# -_4-11.net
KiCad netlist of a schematic drawn in EasyEDA Pro
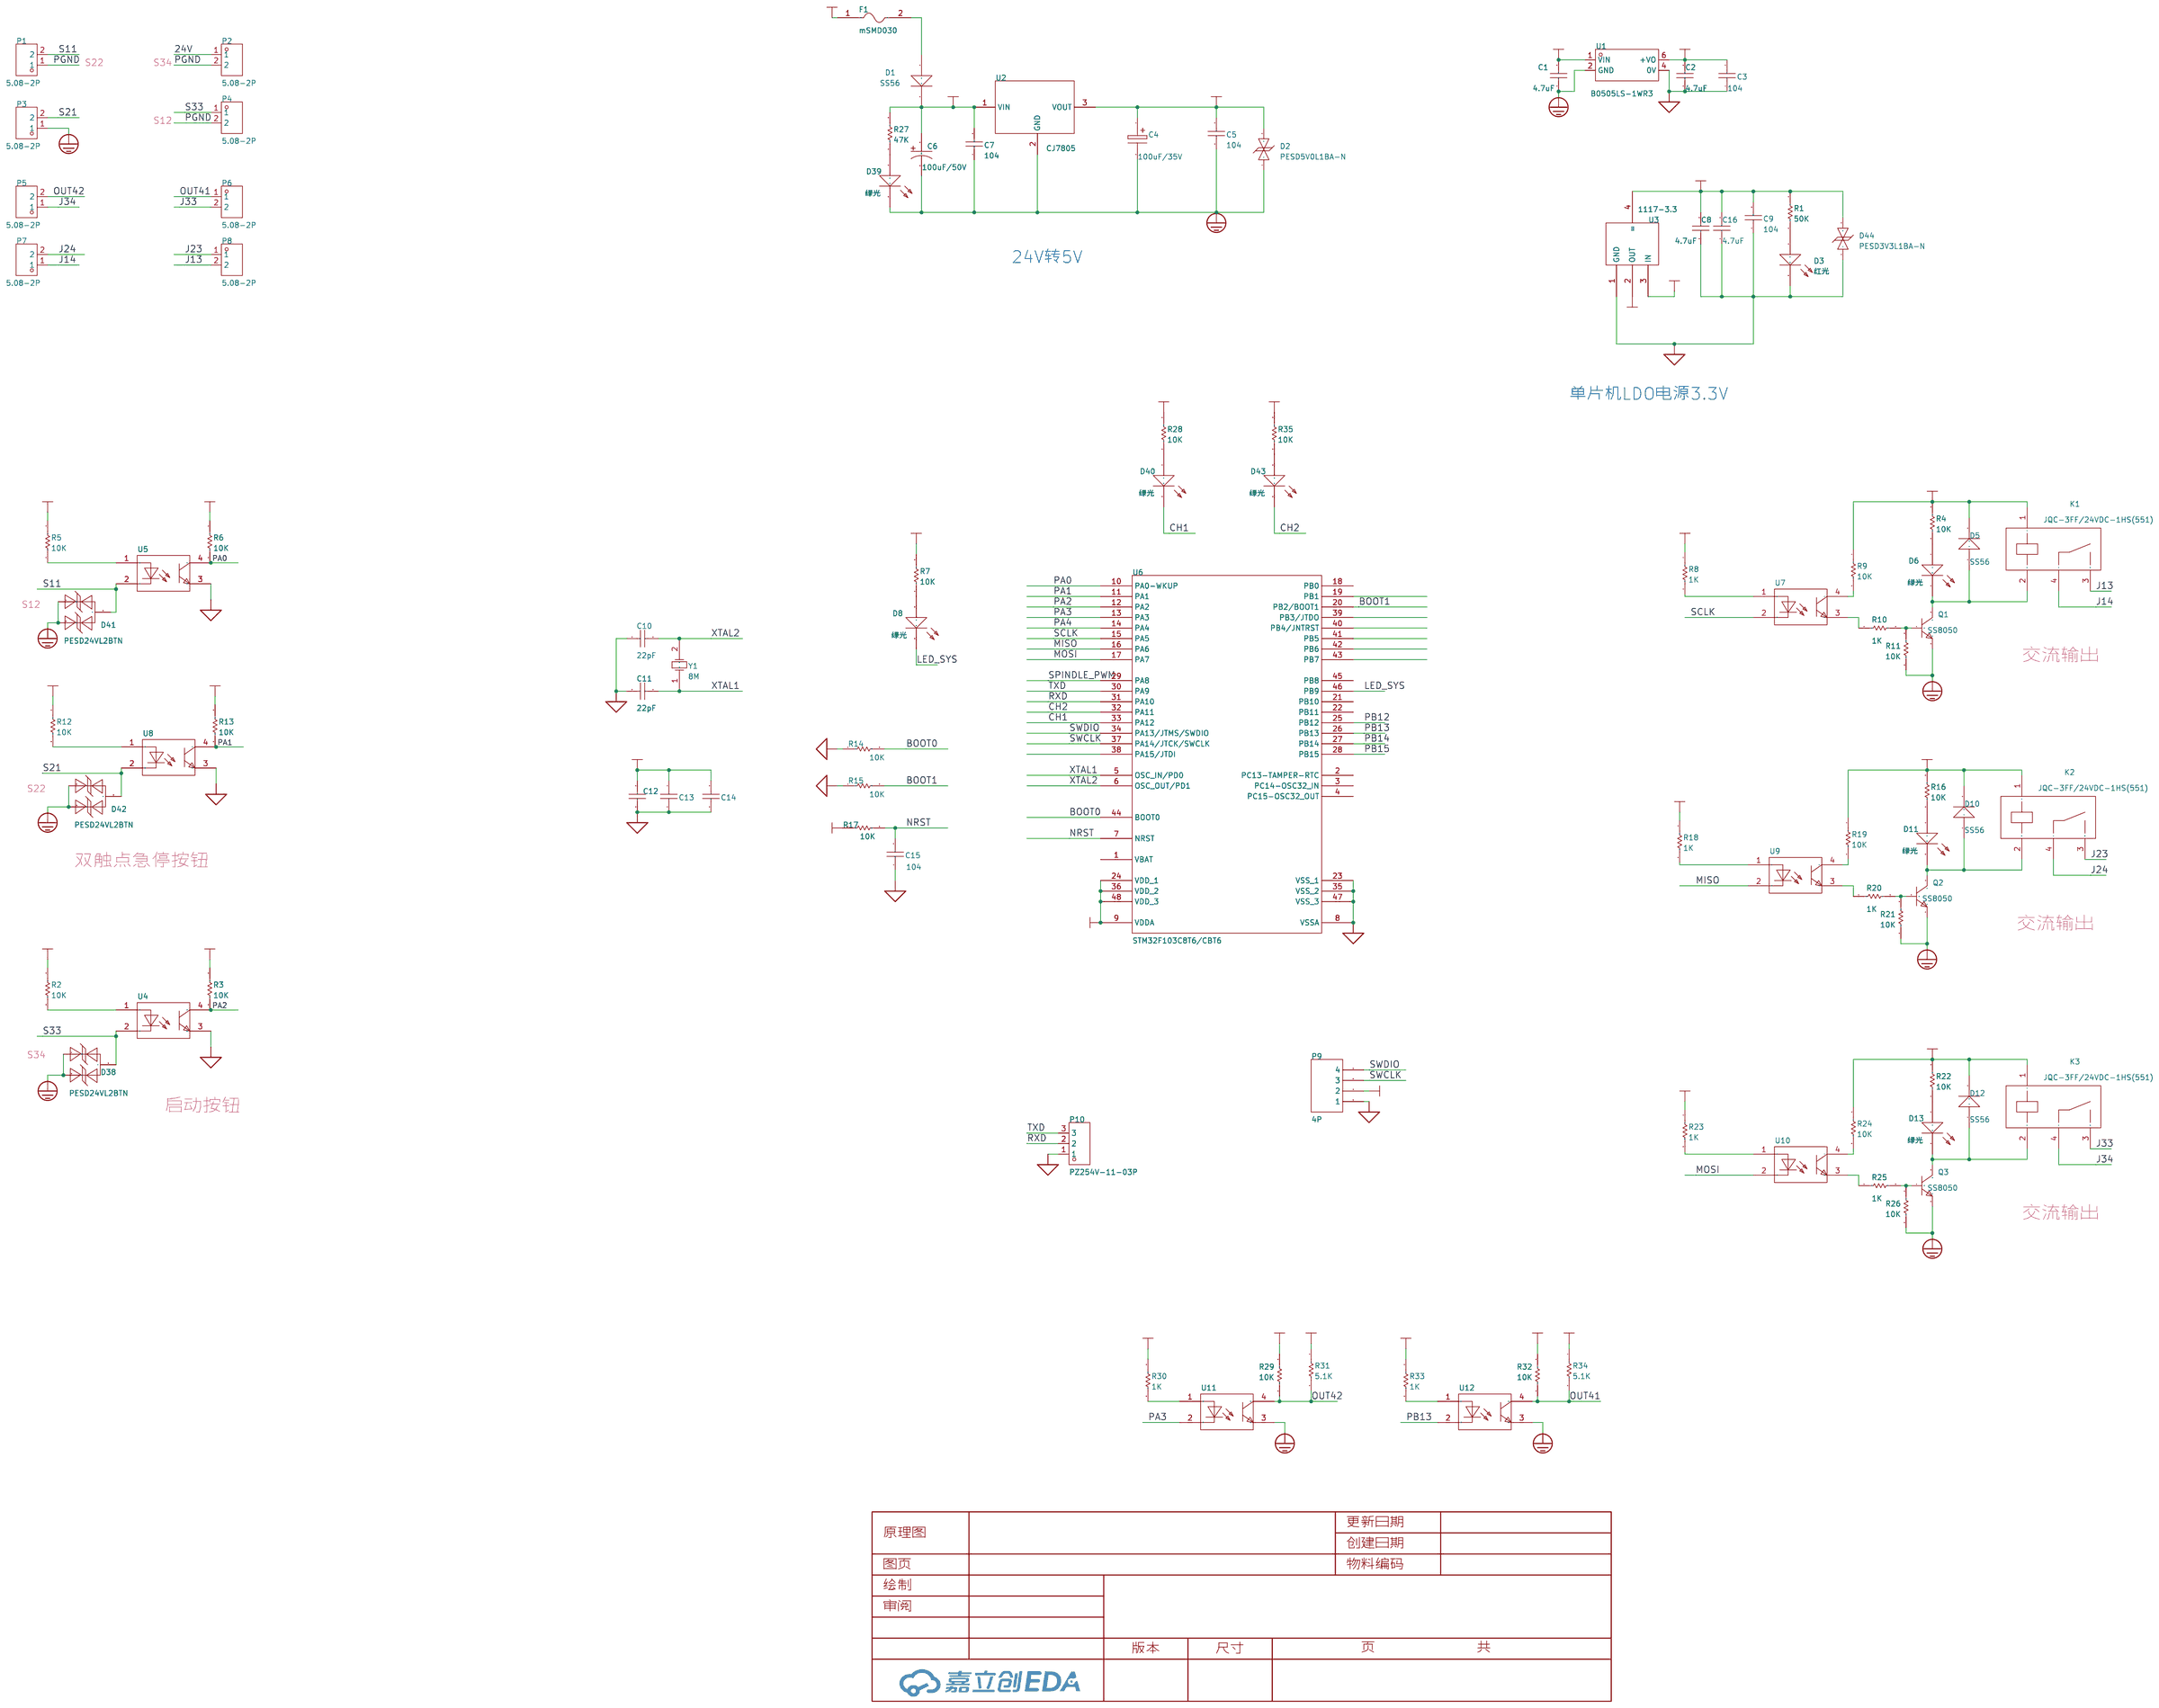
[diagram p0: 主控MCU]
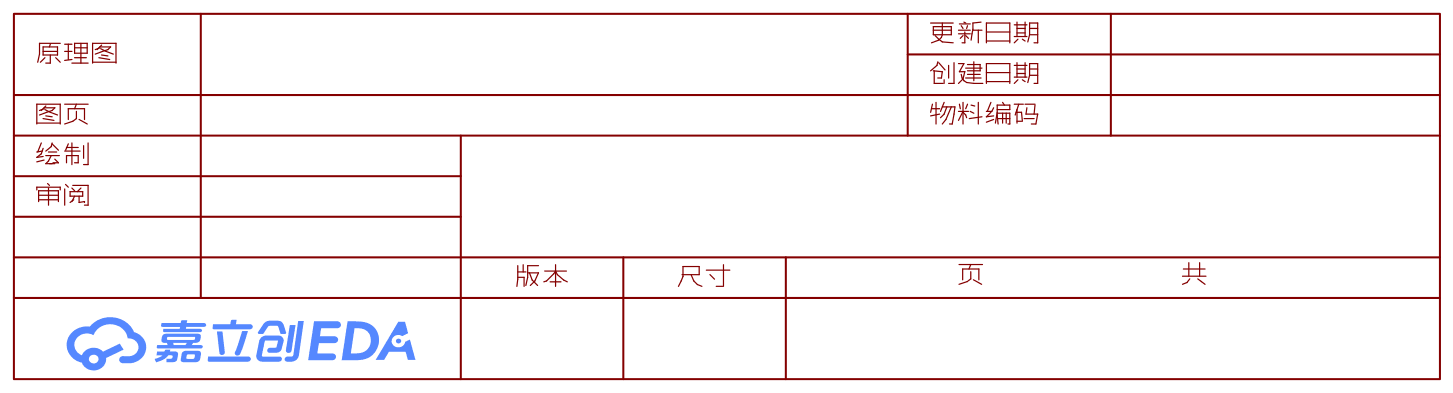
[diagram p1: 电源及控制]

(export (version "E")
  (design (tool "Eeschema 10.0.6"))
  (components
    (comp (ref "C1") (value "4.7uF") (libsource (lib "") (part "CAP_1")))
    (comp (ref "C2") (value "4.7uF") (libsource (lib "") (part "CAP_1")))
    (comp (ref "C3") (value "104") (libsource (lib "") (part "CAP_1")))
    (comp (ref "C4")
      (value "100uF/35V")
      (footprint "easyedapro:0603C")
      (libsource (lib "easyedapro") (part "ELECTRO1"))
    )
    (comp (ref "C5")
      (value "104")
      (footprint "easyedapro:0603C")
      (description "Capacitor (Semiconductor SIM Model)")
      (libsource (lib "easyedapro") (part "Cap Semi"))
    )
    (comp (ref "C6")
      (value "100uF/50V")
      (footprint "easyedapro:CAP-SMD_BD10.0-L10.3-W10.3-LS11.0-R-RD")
      (fields (field (name "Manufacturer Part") "VZH101M1HTR-1008") (field (name "Manufacturer") "lelon(立隆)"))
      (libsource (lib "easyedapro") (part "VZH101M1HTR-1008"))
    )
    (comp (ref "C7")
      (value "104")
      (footprint "easyedapro:0603C")
      (description "Capacitor (Semiconductor SIM Model)")
      (libsource (lib "easyedapro") (part "Cap Semi"))
    )
    (comp (ref "C8") (value "4.7uF") (libsource (lib "") (part "CAP_1")))
    (comp (ref "C9")
      (value "104")
      (footprint "easyedapro:0603C")
      (description "Capacitor (Semiconductor SIM Model)")
      (libsource (lib "easyedapro") (part "Cap Semi"))
    )
    (comp (ref "C10")
      (value "100pF")
      (footprint "easyedapro:0603C")
      (description "Capacitor (Semiconductor SIM Model)")
      (libsource (lib "easyedapro") (part "Cap Semi"))
    )
    (comp (ref "C11")
      (value "100pF")
      (footprint "easyedapro:0603C")
      (description "Capacitor (Semiconductor SIM Model)")
      (libsource (lib "easyedapro") (part "Cap Semi"))
    )
    (comp (ref "C12")
      (value "104")
      (footprint "easyedapro:电解电容贴片6X6")
      (libsource (lib "easyedapro") (part "CAP"))
    )
    (comp (ref "C13")
      (value "104")
      (footprint "easyedapro:电解电容贴片6X6")
      (libsource (lib "easyedapro") (part "CAP"))
    )
    (comp (ref "C14")
      (value "104")
      (footprint "easyedapro:电解电容贴片6X6")
      (libsource (lib "easyedapro") (part "CAP"))
    )
    (comp (ref "C15")
      (value "104")
      (footprint "easyedapro:0603C")
      (description "Capacitor (Semiconductor SIM Model)")
      (libsource (lib "easyedapro") (part "Cap Semi"))
    )
    (comp (ref "C16") (value "4.7uF") (libsource (lib "") (part "CAP_1")))
    (comp (ref "D1")
      (value "SS56")
      (footprint "easyedapro:SMA")
      (libsource (lib "easyedapro") (part "1N4148"))
    )
    (comp (ref "D2")
      (value "PESD5V0L1BA-N")
      (footprint "easyedapro:SOD-523_L1.2-W0.8-LS1.6-BI")
      (description "极性:Bidirectional;反向关断电压（典型值）:5V (Max);击穿电压（最小值）:6V;箝位电压:15V;峰值脉冲电流（10/1000us）:5A (8/20us);")
      (fields (field (name "Manufacturer") "BORN伯恩半导体"))
      (libsource (lib "easyedapro") (part "PESD5V0S1BBN"))
    )
    (comp (ref "D3")
      (value "红光")
      (footprint "easyedapro:0603LED")
      (libsource (lib "easyedapro") (part "LED"))
    )
    (comp (ref "D5")
      (value "SS56")
      (footprint "easyedapro:SMA")
      (libsource (lib "easyedapro") (part "1N4148"))
    )
    (comp (ref "D6")
      (value "绿光")
      (footprint "easyedapro:0603LED")
      (libsource (lib "easyedapro") (part "LED"))
    )
    (comp (ref "D8")
      (value "绿光")
      (footprint "easyedapro:0603LED")
      (libsource (lib "easyedapro") (part "LED"))
    )
    (comp (ref "D10")
      (value "SS56")
      (footprint "easyedapro:SMA")
      (libsource (lib "easyedapro") (part "1N4148"))
    )
    (comp (ref "D11")
      (value "绿光")
      (footprint "easyedapro:0603LED")
      (libsource (lib "easyedapro") (part "LED"))
    )
    (comp (ref "D12")
      (value "SS56")
      (footprint "easyedapro:SMA")
      (libsource (lib "easyedapro") (part "1N4148"))
    )
    (comp (ref "D13")
      (value "绿光")
      (footprint "easyedapro:0603LED")
      (libsource (lib "easyedapro") (part "LED"))
    )
    (comp (ref "D38")
      (value "PESD24VL2BTN")
      (footprint "easyedapro:SOT-23-3_L2.9-W1.6-P1.90-LS2.8-BR")
      (description "极性:Bidirectional;反向关断电压（典型值）:24V (Max);击穿电压（最小值）:26.7V;箝位电压:48V;峰值脉冲电流（10/1000us）:6A (8/20us);")
      (fields (field (name "Manufacturer") "BORN伯恩半导体"))
      (libsource (lib "easyedapro") (part "PESD24VL2BTN"))
    )
    (comp (ref "D39")
      (value "绿光")
      (footprint "easyedapro:0603LED")
      (libsource (lib "easyedapro") (part "LED"))
    )
    (comp (ref "D40")
      (value "绿光")
      (footprint "easyedapro:0603LED")
      (libsource (lib "easyedapro") (part "LED"))
    )
    (comp (ref "D41")
      (value "PESD24VL2BTN")
      (footprint "easyedapro:SOT-23-3_L2.9-W1.6-P1.90-LS2.8-BR")
      (description "极性:Bidirectional;反向关断电压（典型值）:24V (Max);击穿电压（最小值）:26.7V;箝位电压:48V;峰值脉冲电流（10/1000us）:6A (8/20us);")
      (fields (field (name "Manufacturer") "BORN伯恩半导体"))
      (libsource (lib "easyedapro") (part "PESD24VL2BTN"))
    )
    (comp (ref "D42")
      (value "PESD24VL2BTN")
      (footprint "easyedapro:SOT-23-3_L2.9-W1.6-P1.90-LS2.8-BR")
      (description "极性:Bidirectional;反向关断电压（典型值）:24V (Max);击穿电压（最小值）:26.7V;箝位电压:48V;峰值脉冲电流（10/1000us）:6A (8/20us);")
      (fields (field (name "Manufacturer") "BORN伯恩半导体"))
      (libsource (lib "easyedapro") (part "PESD24VL2BTN"))
    )
    (comp (ref "D43")
      (value "绿光")
      (footprint "easyedapro:0603LED")
      (libsource (lib "easyedapro") (part "LED"))
    )
    (comp (ref "D44")
      (value "PESD3V3L1BA-N")
      (footprint "easyedapro:SOD-523_L1.2-W0.8-LS1.6-BI")
      (description "极性:Bidirectional;反向关断电压（典型值）:5V (Max);击穿电压（最小值）:6V;箝位电压:15V;峰值脉冲电流（10/1000us）:5A (8/20us);")
      (fields (field (name "Manufacturer") "BORN伯恩半导体"))
      (libsource (lib "easyedapro") (part "PESD5V0S1BBN"))
    )
    (comp (ref "F1")
      (value "mSMD030")
      (footprint "easyedapro:F1812")
      (description "最大电压:30V;最大电流:100A;保持电流:300mA;跳闸电流:600mA;")
      (fields (field (name "Manufacturer") "台湾陆海"))
      (libsource (lib "easyedapro") (part "mSMD030"))
    )
    (comp (ref "K1")
      (value "JQC-3FF/24VDC-1HS(551)")
      (footprint "easyedapro:RELAY-TH_JQC-3FF-1HXX")
      (description "继电器类型:General Purpose;线圈类型:Non Latching;线圈电压:24VDC;触点形式:SPST-NO;触点的额定电流:15A;")
      (fields (field (name "Manufacturer") "HF(宏发)"))
      (libsource (lib "easyedapro") (part "JQC-3FF/024-1HS"))
    )
    (comp (ref "K2")
      (value "JQC-3FF/24VDC-1HS(551)")
      (footprint "easyedapro:RELAY-TH_JQC-3FF-1HXX")
      (description "继电器类型:General Purpose;线圈类型:Non Latching;线圈电压:24VDC;触点形式:SPST-NO;触点的额定电流:15A;")
      (fields (field (name "Manufacturer") "HF(宏发)"))
      (libsource (lib "easyedapro") (part "JQC-3FF/024-1HS"))
    )
    (comp (ref "K3")
      (value "JQC-3FF/24VDC-1HS(551)")
      (footprint "easyedapro:RELAY-TH_JQC-3FF-1HXX")
      (description "继电器类型:General Purpose;线圈类型:Non Latching;线圈电压:24VDC;触点形式:SPST-NO;触点的额定电流:15A;")
      (fields (field (name "Manufacturer") "HF(宏发)"))
      (libsource (lib "easyedapro") (part "JQC-3FF/024-1HS"))
    )
    (comp (ref "P1")
      (value "5.08-2P")
      (footprint "easyedapro:CONN-TH_2P-P5.08_DB128L-5.08-2P")
      (fields (field (name "Manufacturer") "DIBO(地博电气)"))
      (libsource (lib "easyedapro") (part "DB128L-5.08-2P"))
    )
    (comp (ref "P2")
      (value "5.08-2P")
      (footprint "easyedapro:CONN-TH_2P-P5.08_DB128L-5.08-2P")
      (fields (field (name "Manufacturer") "DIBO(地博电气)"))
      (libsource (lib "easyedapro") (part "DB128L-5.08-2P"))
    )
    (comp (ref "P3")
      (value "5.08-2P")
      (footprint "easyedapro:CONN-TH_2P-P5.08_DB128L-5.08-2P")
      (fields (field (name "Manufacturer") "DIBO(地博电气)"))
      (libsource (lib "easyedapro") (part "DB128L-5.08-2P"))
    )
    (comp (ref "P4")
      (value "5.08-2P")
      (footprint "easyedapro:CONN-TH_2P-P5.08_DB128L-5.08-2P")
      (fields (field (name "Manufacturer") "DIBO(地博电气)"))
      (libsource (lib "easyedapro") (part "DB128L-5.08-2P"))
    )
    (comp (ref "P5")
      (value "5.08-2P")
      (footprint "easyedapro:CONN-TH_2P-P5.08_DB128L-5.08-2P")
      (fields (field (name "Manufacturer") "DIBO(地博电气)"))
      (libsource (lib "easyedapro") (part "DB128L-5.08-2P"))
    )
    (comp (ref "P6")
      (value "5.08-2P")
      (footprint "easyedapro:CONN-TH_2P-P5.08_DB128L-5.08-2P")
      (fields (field (name "Manufacturer") "DIBO(地博电气)"))
      (libsource (lib "easyedapro") (part "DB128L-5.08-2P"))
    )
    (comp (ref "P7")
      (value "5.08-2P")
      (footprint "easyedapro:CONN-TH_2P-P5.08_DB128L-5.08-2P")
      (fields (field (name "Manufacturer") "DIBO(地博电气)"))
      (libsource (lib "easyedapro") (part "DB128L-5.08-2P"))
    )
    (comp (ref "P8")
      (value "5.08-2P")
      (footprint "easyedapro:CONN-TH_2P-P5.08_DB128L-5.08-2P")
      (fields (field (name "Manufacturer") "DIBO(地博电气)"))
      (libsource (lib "easyedapro") (part "DB128L-5.08-2P"))
    )
    (comp (ref "P9") (value "4P") (libsource (lib "easyedapro") (part "4P")))
    (comp (ref "P10")
      (value "PZ254V-11-03P")
      (footprint "easyedapro:HDR-TH_3P-P2.54-V-M")
      (fields (field (name "Manufacturer") "XFCN(兴飞)"))
      (libsource (lib "easyedapro") (part "PZ254V-11-03P_C2937625"))
    )
    (comp (ref "Q1")
      (value "SS8050")
      (footprint "easyedapro:SOT-23-3_L2.9-W1.3-P1.90-LS2.4-BR")
      (fields (field (name "Manufacturer") "CJ（江苏长电/长晶）"))
      (libsource (lib "easyedapro") (part "SS8050_C2150"))
    )
    (comp (ref "Q2")
      (value "SS8050")
      (footprint "easyedapro:SOT-23-3_L2.9-W1.3-P1.90-LS2.4-BR")
      (fields (field (name "Manufacturer") "CJ（江苏长电/长晶）"))
      (libsource (lib "easyedapro") (part "SS8050_C2150"))
    )
    (comp (ref "Q3")
      (value "SS8050")
      (footprint "easyedapro:SOT-23-3_L2.9-W1.3-P1.90-LS2.4-BR")
      (fields (field (name "Manufacturer") "CJ（江苏长电/长晶）"))
      (libsource (lib "easyedapro") (part "SS8050_C2150"))
    )
    (comp (ref "R1")
      (value "50K")
      (footprint "easyedapro:0603R")
      (description "Resistor")
      (libsource (lib "easyedapro") (part "RES"))
    )
    (comp (ref "R2")
      (value "10K")
      (footprint "easyedapro:0603R")
      (description "Resistor")
      (libsource (lib "easyedapro") (part "RES"))
    )
    (comp (ref "R3")
      (value "10K")
      (footprint "easyedapro:0603R")
      (description "Resistor")
      (libsource (lib "easyedapro") (part "RES"))
    )
    (comp (ref "R4")
      (value "10K")
      (footprint "easyedapro:0603R")
      (description "Resistor")
      (libsource (lib "easyedapro") (part "RES"))
    )
    (comp (ref "R5")
      (value "10K")
      (footprint "easyedapro:0603R")
      (description "Resistor")
      (libsource (lib "easyedapro") (part "RES"))
    )
    (comp (ref "R6")
      (value "10K")
      (footprint "easyedapro:0603R")
      (description "Resistor")
      (libsource (lib "easyedapro") (part "RES"))
    )
    (comp (ref "R7")
      (value "10K")
      (footprint "easyedapro:0603R")
      (description "Resistor")
      (libsource (lib "easyedapro") (part "RES"))
    )
    (comp (ref "R8")
      (value "1K")
      (footprint "easyedapro:0603R")
      (description "Resistor")
      (libsource (lib "easyedapro") (part "RES"))
    )
    (comp (ref "R9")
      (value "10K")
      (footprint "easyedapro:0603R")
      (description "Resistor")
      (libsource (lib "easyedapro") (part "RES"))
    )
    (comp (ref "R10")
      (value "1K")
      (footprint "easyedapro:0603R")
      (description "Resistor")
      (libsource (lib "easyedapro") (part "RES"))
    )
    (comp (ref "R11")
      (value "10K")
      (footprint "easyedapro:0603R")
      (description "Resistor")
      (libsource (lib "easyedapro") (part "RES"))
    )
    (comp (ref "R12")
      (value "10K")
      (footprint "easyedapro:0603R")
      (description "Resistor")
      (libsource (lib "easyedapro") (part "RES"))
    )
    (comp (ref "R13")
      (value "10K")
      (footprint "easyedapro:0603R")
      (description "Resistor")
      (libsource (lib "easyedapro") (part "RES"))
    )
    (comp (ref "R14")
      (value "10K")
      (footprint "easyedapro:0603R")
      (description "Resistor")
      (libsource (lib "easyedapro") (part "RES"))
    )
    (comp (ref "R15")
      (value "10K")
      (footprint "easyedapro:0603R")
      (description "Resistor")
      (libsource (lib "easyedapro") (part "RES"))
    )
    (comp (ref "R16")
      (value "10K")
      (footprint "easyedapro:0603R")
      (description "Resistor")
      (libsource (lib "easyedapro") (part "RES"))
    )
    (comp (ref "R17")
      (value "10K")
      (footprint "easyedapro:0603R")
      (description "Resistor")
      (libsource (lib "easyedapro") (part "RES"))
    )
    (comp (ref "R18")
      (value "1K")
      (footprint "easyedapro:0603R")
      (description "Resistor")
      (libsource (lib "easyedapro") (part "RES"))
    )
    (comp (ref "R19")
      (value "10K")
      (footprint "easyedapro:0603R")
      (description "Resistor")
      (libsource (lib "easyedapro") (part "RES"))
    )
    (comp (ref "R20")
      (value "1K")
      (footprint "easyedapro:0603R")
      (description "Resistor")
      (libsource (lib "easyedapro") (part "RES"))
    )
    (comp (ref "R21")
      (value "10K")
      (footprint "easyedapro:0603R")
      (description "Resistor")
      (libsource (lib "easyedapro") (part "RES"))
    )
    (comp (ref "R22")
      (value "10K")
      (footprint "easyedapro:0603R")
      (description "Resistor")
      (libsource (lib "easyedapro") (part "RES"))
    )
    (comp (ref "R23")
      (value "1K")
      (footprint "easyedapro:0603R")
      (description "Resistor")
      (libsource (lib "easyedapro") (part "RES"))
    )
    (comp (ref "R24")
      (value "10K")
      (footprint "easyedapro:0603R")
      (description "Resistor")
      (libsource (lib "easyedapro") (part "RES"))
    )
    (comp (ref "R25")
      (value "1K")
      (footprint "easyedapro:0603R")
      (description "Resistor")
      (libsource (lib "easyedapro") (part "RES"))
    )
    (comp (ref "R26")
      (value "10K")
      (footprint "easyedapro:0603R")
      (description "Resistor")
      (libsource (lib "easyedapro") (part "RES"))
    )
    (comp (ref "R27")
      (value "47K")
      (footprint "easyedapro:0603R")
      (description "Resistor")
      (libsource (lib "easyedapro") (part "RES"))
    )
    (comp (ref "R28")
      (value "10K")
      (footprint "easyedapro:0603R")
      (description "Resistor")
      (libsource (lib "easyedapro") (part "RES"))
    )
    (comp (ref "R29")
      (value "10K")
      (footprint "easyedapro:0603R")
      (description "Resistor")
      (libsource (lib "easyedapro") (part "RES"))
    )
    (comp (ref "R30")
      (value "1K")
      (footprint "easyedapro:0603R")
      (description "Resistor")
      (libsource (lib "easyedapro") (part "RES"))
    )
    (comp (ref "R31")
      (value "10K")
      (footprint "easyedapro:0603R")
      (description "Resistor")
      (libsource (lib "easyedapro") (part "RES"))
    )
    (comp (ref "R32")
      (value "10K")
      (footprint "easyedapro:0603R")
      (description "Resistor")
      (libsource (lib "easyedapro") (part "RES"))
    )
    (comp (ref "R33")
      (value "1K")
      (footprint "easyedapro:0603R")
      (description "Resistor")
      (libsource (lib "easyedapro") (part "RES"))
    )
    (comp (ref "R34")
      (value "10K")
      (footprint "easyedapro:0603R")
      (description "Resistor")
      (libsource (lib "easyedapro") (part "RES"))
    )
    (comp (ref "R35")
      (value "10K")
      (footprint "easyedapro:0603R")
      (description "Resistor")
      (libsource (lib "easyedapro") (part "RES"))
    )
    (comp (ref "U1")
      (value "B0505LS-1WR3")
      (footprint "easyedapro:PWRM-TH_BXXXXLS-1WR3")
      (description "100%国产化器件，高可靠性，具备ROHS、REACH、CE认证产品")
      (fields (field (name "Manufacturer") "DEXU(德旭电子)"))
      (libsource (lib "easyedapro") (part "B0505LS-1WR3_C909800"))
    )
    (comp (ref "U2")
      (value "CJ7805")
      (footprint "easyedapro:TO-263-2")
      (libsource (lib "easyedapro") (part "7805"))
    )
    (comp (ref "U3")
      (value "1117-3.3")
      (footprint "easyedapro:SOT-223")
      (libsource (lib "easyedapro") (part "LM1117"))
    )
    (comp (ref "U4")
      (value "LTV-357T-C")
      (footprint "easyedapro:SOP-4_L4.4-W3.9-P2.54-LS7.0-TL")
      (fields (field (name "Manufacturer") "LITEON(光宝)"))
      (libsource (lib "easyedapro") (part "LTV-357T-C"))
    )
    (comp (ref "U5")
      (value "LTV-357T-C")
      (footprint "easyedapro:SOP-4_L4.4-W3.9-P2.54-LS7.0-TL")
      (fields (field (name "Manufacturer") "LITEON(光宝)"))
      (libsource (lib "easyedapro") (part "LTV-357T-C"))
    )
    (comp (ref "U6")
      (value "STM32F103C8T6/CBT6")
      (footprint "easyedapro:LQFP48")
      (description "STM32 ARM-based 32-bit MCU with 32 Kbytes Flash, 48-pin LQFP, Industrial Temperature")
      (libsource (lib "easyedapro") (part "STM32F103C6T6"))
    )
    (comp (ref "U7")
      (value "LTV-357T-C")
      (footprint "easyedapro:SOP-4_L4.4-W3.9-P2.54-LS7.0-TL")
      (fields (field (name "Manufacturer") "LITEON(光宝)"))
      (libsource (lib "easyedapro") (part "LTV-357T-C"))
    )
    (comp (ref "U8")
      (value "LTV-357T-C")
      (footprint "easyedapro:SOP-4_L4.4-W3.9-P2.54-LS7.0-TL")
      (fields (field (name "Manufacturer") "LITEON(光宝)"))
      (libsource (lib "easyedapro") (part "LTV-357T-C"))
    )
    (comp (ref "U9")
      (value "LTV-357T-C")
      (footprint "easyedapro:SOP-4_L4.4-W3.9-P2.54-LS7.0-TL")
      (fields (field (name "Manufacturer") "LITEON(光宝)"))
      (libsource (lib "easyedapro") (part "LTV-357T-C"))
    )
    (comp (ref "U10")
      (value "LTV-357T-C")
      (footprint "easyedapro:SOP-4_L4.4-W3.9-P2.54-LS7.0-TL")
      (fields (field (name "Manufacturer") "LITEON(光宝)"))
      (libsource (lib "easyedapro") (part "LTV-357T-C"))
    )
    (comp (ref "U11")
      (value "LTV-357T-C")
      (footprint "easyedapro:SOP-4_L4.4-W3.9-P2.54-LS7.0-TL")
      (fields (field (name "Manufacturer") "LITEON(光宝)"))
      (libsource (lib "easyedapro") (part "LTV-357T-C"))
    )
    (comp (ref "U12")
      (value "LTV-357T-C")
      (footprint "easyedapro:SOP-4_L4.4-W3.9-P2.54-LS7.0-TL")
      (fields (field (name "Manufacturer") "LITEON(光宝)"))
      (libsource (lib "easyedapro") (part "LTV-357T-C"))
    )
    (comp (ref "Y1")
      (value "8M")
      (footprint "easyedapro:晶振贴片49SSMD")
      (description "Crystal Oscillator")
      (libsource (lib "easyedapro") (part "XTAL"))
    )
  )
  (nets
    (net (code "1") (name "3V3") (class "Default")
      (node (ref "C12") (pin "2") (pinfunction "2_2") (pintype "unspecified"))
      (node (ref "C13") (pin "2") (pinfunction "2_2") (pintype "unspecified"))
      (node (ref "C14") (pin "2") (pinfunction "2_2") (pintype "unspecified"))
      (node (ref "C16") (pin "2") (pinfunction "2_2") (pintype "input"))
      (node (ref "C8") (pin "2") (pinfunction "2_2") (pintype "input"))
      (node (ref "C9") (pin "2") (pinfunction "2_2") (pintype "unspecified"))
      (node (ref "D44") (pin "2") (pinfunction "2_2") (pintype "input"))
      (node (ref "P9") (pin "2") (pinfunction "2_2") (pintype "input"))
      (node (ref "R1") (pin "1") (pinfunction "1_1") (pintype "unspecified"))
      (node (ref "R13") (pin "1") (pinfunction "1_1") (pintype "unspecified"))
      (node (ref "R17") (pin "1") (pinfunction "1_1") (pintype "unspecified"))
      (node (ref "R18") (pin "1") (pinfunction "1_1") (pintype "unspecified"))
      (node (ref "R23") (pin "1") (pinfunction "1_1") (pintype "unspecified"))
      (node (ref "R28") (pin "2") (pinfunction "2_2") (pintype "unspecified"))
      (node (ref "R3") (pin "1") (pinfunction "1_1") (pintype "unspecified"))
      (node (ref "R30") (pin "1") (pinfunction "1_1") (pintype "unspecified"))
      (node (ref "R33") (pin "1") (pinfunction "1_1") (pintype "unspecified"))
      (node (ref "R35") (pin "2") (pinfunction "2_2") (pintype "unspecified"))
      (node (ref "R6") (pin "1") (pinfunction "1_1") (pintype "unspecified"))
      (node (ref "R7") (pin "2") (pinfunction "2_2") (pintype "unspecified"))
      (node (ref "R8") (pin "1") (pinfunction "1_1") (pintype "unspecified"))
      (node (ref "U3") (pin "2") (pinfunction "OUT_2") (pintype "unspecified"))
      (node (ref "U3") (pin "4") (pinfunction "=_4") (pintype "unspecified"))
      (node (ref "U6") (pin "24") (pinfunction "VDD_1_24") (pintype "unspecified"))
      (node (ref "U6") (pin "36") (pinfunction "VDD_2_36") (pintype "unspecified"))
      (node (ref "U6") (pin "48") (pinfunction "VDD_3_48") (pintype "unspecified"))
      (node (ref "U6") (pin "9") (pinfunction "VDDA_9") (pintype "unspecified"))
    )
    (net (code "2") (name "5V_MCU") (class "Default")
      (node (ref "C2") (pin "2") (pinfunction "2_2") (pintype "input"))
      (node (ref "C3") (pin "2") (pinfunction "2_2") (pintype "input"))
      (node (ref "U1") (pin "6") (pinfunction "+VO_6") (pintype "unspecified"))
      (node (ref "U3") (pin "3") (pinfunction "IN_3") (pintype "unspecified"))
    )
    (net (code "3") (name "5V_VCC") (class "Default")
      (node (ref "C1") (pin "2") (pinfunction "2_2") (pintype "input"))
      (node (ref "C4") (pin "1") (pintype "unspecified"))
      (node (ref "C5") (pin "2") (pinfunction "2_2") (pintype "unspecified"))
      (node (ref "D2") (pin "2") (pinfunction "2_2") (pintype "input"))
      (node (ref "R31") (pin "1") (pinfunction "1_1") (pintype "unspecified"))
      (node (ref "R34") (pin "1") (pinfunction "1_1") (pintype "unspecified"))
      (node (ref "U1") (pin "1") (pinfunction "VIN_1") (pintype "unspecified"))
      (node (ref "U2") (pin "3") (pinfunction "VOUT_3") (pintype "unspecified"))
    )
    (net (code "4") (name "24V") (class "Default")
      (node (ref "F1") (pin "1") (pinfunction "1_1") (pintype "input"))
      (node (ref "P2") (pin "1") (pinfunction "1_1") (pintype "input"))
    )
    (net (code "5") (name "BOOT0") (class "Default")
      (node (ref "R14") (pin "2") (pinfunction "2_2") (pintype "unspecified"))
      (node (ref "U6") (pin "44") (pinfunction "BOOT0_44") (pintype "input"))
    )
    (net (code "6") (name "BOOT1") (class "Default")
      (node (ref "R15") (pin "2") (pinfunction "2_2") (pintype "unspecified"))
      (node (ref "U6") (pin "20") (pinfunction "PB2/BOOT1_20") (pintype "bidirectional"))
    )
    (net (code "7") (name "CH1") (class "Default")
      (node (ref "D40") (pin "2") (pinfunction "2_2") (pintype "unspecified"))
      (node (ref "U6") (pin "33") (pinfunction "PA12_33") (pintype "bidirectional"))
    )
    (net (code "8") (name "CH2") (class "Default")
      (node (ref "D43") (pin "2") (pinfunction "2_2") (pintype "unspecified"))
      (node (ref "U6") (pin "32") (pinfunction "PA11_32") (pintype "bidirectional"))
    )
    (net (code "9") (name "J13") (class "Default")
      (node (ref "K1") (pin "3") (pinfunction "3_3") (pintype "input"))
      (node (ref "P8") (pin "2") (pinfunction "2_2") (pintype "input"))
    )
    (net (code "10") (name "J14") (class "Default")
      (node (ref "K1") (pin "4") (pinfunction "4_4") (pintype "input"))
      (node (ref "P7") (pin "1") (pinfunction "1_1") (pintype "input"))
    )
    (net (code "11") (name "J23") (class "Default")
      (node (ref "K2") (pin "3") (pinfunction "3_3") (pintype "input"))
      (node (ref "P8") (pin "1") (pinfunction "1_1") (pintype "input"))
    )
    (net (code "12") (name "J24") (class "Default")
      (node (ref "K2") (pin "4") (pinfunction "4_4") (pintype "input"))
      (node (ref "P7") (pin "2") (pinfunction "2_2") (pintype "input"))
    )
    (net (code "13") (name "J33") (class "Default")
      (node (ref "K3") (pin "3") (pinfunction "3_3") (pintype "input"))
      (node (ref "P6") (pin "2") (pinfunction "2_2") (pintype "input"))
    )
    (net (code "14") (name "J34") (class "Default")
      (node (ref "K3") (pin "4") (pinfunction "4_4") (pintype "input"))
      (node (ref "P5") (pin "1") (pinfunction "1_1") (pintype "input"))
    )
    (net (code "15") (name "LED_SYS") (class "Default")
      (node (ref "D8") (pin "2") (pinfunction "2_2") (pintype "unspecified"))
      (node (ref "U6") (pin "46") (pinfunction "PB9_46") (pintype "bidirectional"))
    )
    (net (code "16") (name "MISO") (class "Default")
      (node (ref "U6") (pin "16") (pinfunction "PA6_16") (pintype "bidirectional"))
      (node (ref "U9") (pin "2") (pinfunction "2_2") (pintype "unspecified"))
    )
    (net (code "17") (name "MOSI") (class "Default")
      (node (ref "U10") (pin "2") (pinfunction "2_2") (pintype "unspecified"))
      (node (ref "U6") (pin "17") (pinfunction "PA7_17") (pintype "bidirectional"))
    )
    (net (code "18") (name "NRST") (class "Default")
      (node (ref "C15") (pin "2") (pinfunction "2_2") (pintype "unspecified"))
      (node (ref "R17") (pin "2") (pinfunction "2_2") (pintype "unspecified"))
      (node (ref "U6") (pin "7") (pinfunction "NRST_7") (pintype "bidirectional"))
    )
    (net (code "19") (name "Net-(D1-Pad1)") (class "Default")
      (node (ref "D1") (pin "1") (pinfunction "1_1") (pintype "unspecified"))
      (node (ref "F1") (pin "2") (pinfunction "2_2") (pintype "input"))
    )
    (net (code "20") (name "Net-(D3-Pad1)") (class "Default")
      (node (ref "D3") (pin "1") (pinfunction "1_1") (pintype "unspecified"))
      (node (ref "R1") (pin "2") (pinfunction "2_2") (pintype "unspecified"))
    )
    (net (code "21") (name "Net-(D6-Pad1)") (class "Default")
      (node (ref "D6") (pin "1") (pinfunction "1_1") (pintype "unspecified"))
      (node (ref "R4") (pin "1") (pinfunction "1_1") (pintype "unspecified"))
    )
    (net (code "22") (name "Net-(D8-Pad1)") (class "Default")
      (node (ref "D8") (pin "1") (pinfunction "1_1") (pintype "unspecified"))
      (node (ref "R7") (pin "1") (pinfunction "1_1") (pintype "unspecified"))
    )
    (net (code "23") (name "Net-(D11-Pad1)") (class "Default")
      (node (ref "D11") (pin "1") (pinfunction "1_1") (pintype "unspecified"))
      (node (ref "R16") (pin "1") (pinfunction "1_1") (pintype "unspecified"))
    )
    (net (code "24") (name "Net-(D13-Pad1)") (class "Default")
      (node (ref "D13") (pin "1") (pinfunction "1_1") (pintype "unspecified"))
      (node (ref "R22") (pin "1") (pinfunction "1_1") (pintype "unspecified"))
    )
    (net (code "25") (name "Net-(D39-Pad1)") (class "Default")
      (node (ref "D39") (pin "1") (pinfunction "1_1") (pintype "unspecified"))
      (node (ref "R27") (pin "1") (pinfunction "1_1") (pintype "unspecified"))
    )
    (net (code "26") (name "Net-(D40-Pad1)") (class "Default")
      (node (ref "D40") (pin "1") (pinfunction "1_1") (pintype "unspecified"))
      (node (ref "R28") (pin "1") (pinfunction "1_1") (pintype "unspecified"))
    )
    (net (code "27") (name "Net-(D43-Pad1)") (class "Default")
      (node (ref "D43") (pin "1") (pinfunction "1_1") (pintype "unspecified"))
      (node (ref "R35") (pin "1") (pinfunction "1_1") (pintype "unspecified"))
    )
    (net (code "28") (name "Net-(Q1-B)") (class "Default")
      (node (ref "Q1") (pin "1") (pinfunction "B_1") (pintype "input"))
      (node (ref "R10") (pin "2") (pinfunction "2_2") (pintype "unspecified"))
      (node (ref "R11") (pin "1") (pinfunction "1_1") (pintype "unspecified"))
    )
    (net (code "29") (name "Net-(Q1-C)") (class "Default")
      (node (ref "D5") (pin "1") (pinfunction "1_1") (pintype "unspecified"))
      (node (ref "D6") (pin "2") (pinfunction "2_2") (pintype "unspecified"))
      (node (ref "K1") (pin "2") (pinfunction "2_2") (pintype "input"))
      (node (ref "Q1") (pin "3") (pinfunction "C_3") (pintype "input"))
    )
    (net (code "30") (name "Net-(Q2-B)") (class "Default")
      (node (ref "Q2") (pin "1") (pinfunction "B_1") (pintype "input"))
      (node (ref "R20") (pin "2") (pinfunction "2_2") (pintype "unspecified"))
      (node (ref "R21") (pin "1") (pinfunction "1_1") (pintype "unspecified"))
    )
    (net (code "31") (name "Net-(Q2-C)") (class "Default")
      (node (ref "D10") (pin "1") (pinfunction "1_1") (pintype "unspecified"))
      (node (ref "D11") (pin "2") (pinfunction "2_2") (pintype "unspecified"))
      (node (ref "K2") (pin "2") (pinfunction "2_2") (pintype "input"))
      (node (ref "Q2") (pin "3") (pinfunction "C_3") (pintype "input"))
    )
    (net (code "32") (name "Net-(Q3-B)") (class "Default")
      (node (ref "Q3") (pin "1") (pinfunction "B_1") (pintype "input"))
      (node (ref "R25") (pin "2") (pinfunction "2_2") (pintype "unspecified"))
      (node (ref "R26") (pin "1") (pinfunction "1_1") (pintype "unspecified"))
    )
    (net (code "33") (name "Net-(Q3-C)") (class "Default")
      (node (ref "D12") (pin "1") (pinfunction "1_1") (pintype "unspecified"))
      (node (ref "D13") (pin "2") (pinfunction "2_2") (pintype "unspecified"))
      (node (ref "K3") (pin "2") (pinfunction "2_2") (pintype "input"))
      (node (ref "Q3") (pin "3") (pinfunction "C_3") (pintype "input"))
    )
    (net (code "34") (name "Net-(R2-Pad2)") (class "Default")
      (node (ref "R2") (pin "2") (pinfunction "2_2") (pintype "unspecified"))
      (node (ref "U4") (pin "1") (pinfunction "1_1") (pintype "unspecified"))
    )
    (net (code "35") (name "Net-(R5-Pad2)") (class "Default")
      (node (ref "R5") (pin "2") (pinfunction "2_2") (pintype "unspecified"))
      (node (ref "U5") (pin "1") (pinfunction "1_1") (pintype "unspecified"))
    )
    (net (code "36") (name "Net-(R8-Pad2)") (class "Default")
      (node (ref "R8") (pin "2") (pinfunction "2_2") (pintype "unspecified"))
      (node (ref "U7") (pin "1") (pinfunction "1_1") (pintype "unspecified"))
    )
    (net (code "37") (name "Net-(R9-Pad2)") (class "Default")
      (node (ref "R9") (pin "2") (pinfunction "2_2") (pintype "unspecified"))
      (node (ref "U7") (pin "4") (pinfunction "4_4") (pintype "unspecified"))
    )
    (net (code "38") (name "Net-(R10-Pad1)") (class "Default")
      (node (ref "R10") (pin "1") (pinfunction "1_1") (pintype "unspecified"))
      (node (ref "U7") (pin "3") (pinfunction "3_3") (pintype "unspecified"))
    )
    (net (code "39") (name "Net-(R12-Pad2)") (class "Default")
      (node (ref "R12") (pin "2") (pinfunction "2_2") (pintype "unspecified"))
      (node (ref "U8") (pin "1") (pinfunction "1_1") (pintype "unspecified"))
    )
    (net (code "40") (name "Net-(R18-Pad2)") (class "Default")
      (node (ref "R18") (pin "2") (pinfunction "2_2") (pintype "unspecified"))
      (node (ref "U9") (pin "1") (pinfunction "1_1") (pintype "unspecified"))
    )
    (net (code "41") (name "Net-(R19-Pad2)") (class "Default")
      (node (ref "R19") (pin "2") (pinfunction "2_2") (pintype "unspecified"))
      (node (ref "U9") (pin "4") (pinfunction "4_4") (pintype "unspecified"))
    )
    (net (code "42") (name "Net-(R20-Pad1)") (class "Default")
      (node (ref "R20") (pin "1") (pinfunction "1_1") (pintype "unspecified"))
      (node (ref "U9") (pin "3") (pinfunction "3_3") (pintype "unspecified"))
    )
    (net (code "43") (name "Net-(R23-Pad2)") (class "Default")
      (node (ref "R23") (pin "2") (pinfunction "2_2") (pintype "unspecified"))
      (node (ref "U10") (pin "1") (pinfunction "1_1") (pintype "unspecified"))
    )
    (net (code "44") (name "Net-(R24-Pad2)") (class "Default")
      (node (ref "R24") (pin "2") (pinfunction "2_2") (pintype "unspecified"))
      (node (ref "U10") (pin "4") (pinfunction "4_4") (pintype "unspecified"))
    )
    (net (code "45") (name "Net-(R25-Pad1)") (class "Default")
      (node (ref "R25") (pin "1") (pinfunction "1_1") (pintype "unspecified"))
      (node (ref "U10") (pin "3") (pinfunction "3_3") (pintype "unspecified"))
    )
    (net (code "46") (name "Net-(R30-Pad2)") (class "Default")
      (node (ref "R30") (pin "2") (pinfunction "2_2") (pintype "unspecified"))
      (node (ref "U11") (pin "1") (pinfunction "1_1") (pintype "unspecified"))
    )
    (net (code "47") (name "Net-(R33-Pad2)") (class "Default")
      (node (ref "R33") (pin "2") (pinfunction "2_2") (pintype "unspecified"))
      (node (ref "U12") (pin "1") (pinfunction "1_1") (pintype "unspecified"))
    )
    (net (code "48") (name "OUT41") (class "Default")
      (node (ref "P6") (pin "1") (pinfunction "1_1") (pintype "input"))
      (node (ref "R32") (pin "2") (pinfunction "2_2") (pintype "unspecified"))
      (node (ref "R34") (pin "2") (pinfunction "2_2") (pintype "unspecified"))
      (node (ref "U12") (pin "4") (pinfunction "4_4") (pintype "unspecified"))
    )
    (net (code "49") (name "OUT42") (class "Default")
      (node (ref "P5") (pin "2") (pinfunction "2_2") (pintype "input"))
      (node (ref "R29") (pin "2") (pinfunction "2_2") (pintype "unspecified"))
      (node (ref "R31") (pin "2") (pinfunction "2_2") (pintype "unspecified"))
      (node (ref "U11") (pin "4") (pinfunction "4_4") (pintype "unspecified"))
    )
    (net (code "50") (name "PA0") (class "Default")
      (node (ref "R6") (pin "2") (pinfunction "2_2") (pintype "unspecified"))
      (node (ref "U5") (pin "4") (pinfunction "4_4") (pintype "unspecified"))
      (node (ref "U6") (pin "10") (pinfunction "PA0-WKUP_10") (pintype "bidirectional"))
    )
    (net (code "51") (name "PA1") (class "Default")
      (node (ref "R13") (pin "2") (pinfunction "2_2") (pintype "unspecified"))
      (node (ref "U6") (pin "11") (pinfunction "PA1_11") (pintype "bidirectional"))
      (node (ref "U8") (pin "4") (pinfunction "4_4") (pintype "unspecified"))
    )
    (net (code "52") (name "PA2") (class "Default")
      (node (ref "R3") (pin "2") (pinfunction "2_2") (pintype "unspecified"))
      (node (ref "U4") (pin "4") (pinfunction "4_4") (pintype "unspecified"))
      (node (ref "U6") (pin "12") (pinfunction "PA2_12") (pintype "bidirectional"))
    )
    (net (code "53") (name "PA3") (class "Default")
      (node (ref "U11") (pin "2") (pinfunction "2_2") (pintype "unspecified"))
      (node (ref "U6") (pin "13") (pinfunction "PA3_13") (pintype "bidirectional"))
    )
    (net (code "54") (name "PA4") (class "Default")
      (node (ref "U6") (pin "14") (pinfunction "PA4_14") (pintype "bidirectional"))
    )
    (net (code "55") (name "PB12") (class "Default")
      (node (ref "U6") (pin "25") (pinfunction "PB12_25") (pintype "bidirectional"))
    )
    (net (code "56") (name "PB13") (class "Default")
      (node (ref "U12") (pin "2") (pinfunction "2_2") (pintype "unspecified"))
      (node (ref "U6") (pin "26") (pinfunction "PB13_26") (pintype "bidirectional"))
    )
    (net (code "57") (name "PB14") (class "Default")
      (node (ref "U6") (pin "27") (pinfunction "PB14_27") (pintype "bidirectional"))
    )
    (net (code "58") (name "PB15") (class "Default")
      (node (ref "U6") (pin "28") (pinfunction "PB15_28") (pintype "bidirectional"))
    )
    (net (code "59") (name "PGND") (class "Default")
      (node (ref "C1") (pin "1") (pinfunction "1_1") (pintype "input"))
      (node (ref "C4") (pin "2") (pintype "unspecified"))
      (node (ref "C5") (pin "1") (pinfunction "1_1") (pintype "unspecified"))
      (node (ref "C6") (pin "2") (pinfunction "2_2") (pintype "input"))
      (node (ref "C7") (pin "1") (pinfunction "1_1") (pintype "unspecified"))
      (node (ref "D2") (pin "1") (pinfunction "1_1") (pintype "input"))
      (node (ref "D38") (pin "1") (pinfunction "K_1") (pintype "input"))
      (node (ref "D38") (pin "2") (pinfunction "K_2") (pintype "input"))
      (node (ref "D39") (pin "2") (pinfunction "2_2") (pintype "unspecified"))
      (node (ref "D41") (pin "1") (pinfunction "K_1") (pintype "input"))
      (node (ref "D41") (pin "2") (pinfunction "K_2") (pintype "input"))
      (node (ref "D42") (pin "1") (pinfunction "K_1") (pintype "input"))
      (node (ref "D42") (pin "2") (pinfunction "K_2") (pintype "input"))
      (node (ref "P1") (pin "1") (pinfunction "1_1") (pintype "input"))
      (node (ref "P2") (pin "2") (pinfunction "2_2") (pintype "input"))
      (node (ref "P3") (pin "1") (pinfunction "1_1") (pintype "input"))
      (node (ref "P4") (pin "2") (pinfunction "2_2") (pintype "input"))
      (node (ref "Q1") (pin "2") (pinfunction "E_2") (pintype "input"))
      (node (ref "Q2") (pin "2") (pinfunction "E_2") (pintype "input"))
      (node (ref "Q3") (pin "2") (pinfunction "E_2") (pintype "input"))
      (node (ref "R11") (pin "2") (pinfunction "2_2") (pintype "unspecified"))
      (node (ref "R21") (pin "2") (pinfunction "2_2") (pintype "unspecified"))
      (node (ref "R26") (pin "2") (pinfunction "2_2") (pintype "unspecified"))
      (node (ref "U1") (pin "2") (pinfunction "GND_2") (pintype "unspecified"))
      (node (ref "U11") (pin "3") (pinfunction "3_3") (pintype "unspecified"))
      (node (ref "U12") (pin "3") (pinfunction "3_3") (pintype "unspecified"))
      (node (ref "U2") (pin "2") (pinfunction "GND_2") (pintype "unspecified"))
    )
    (net (code "60") (name "RXD") (class "Default")
      (node (ref "P10") (pin "2") (pinfunction "2_2") (pintype "unspecified"))
      (node (ref "U6") (pin "31") (pinfunction "PA10_31") (pintype "bidirectional"))
    )
    (net (code "61") (name "S11") (class "Default")
      (node (ref "D41") (pin "3") (pinfunction "A_3") (pintype "input"))
      (node (ref "P1") (pin "2") (pinfunction "2_2") (pintype "input"))
      (node (ref "U5") (pin "2") (pinfunction "2_2") (pintype "unspecified"))
    )
    (net (code "62") (name "S21") (class "Default")
      (node (ref "D42") (pin "3") (pinfunction "A_3") (pintype "input"))
      (node (ref "P3") (pin "2") (pinfunction "2_2") (pintype "input"))
      (node (ref "U8") (pin "2") (pinfunction "2_2") (pintype "unspecified"))
    )
    (net (code "63") (name "S33") (class "Default")
      (node (ref "D38") (pin "3") (pinfunction "A_3") (pintype "input"))
      (node (ref "P4") (pin "1") (pinfunction "1_1") (pintype "input"))
      (node (ref "U4") (pin "2") (pinfunction "2_2") (pintype "unspecified"))
    )
    (net (code "64") (name "SCLK") (class "Default")
      (node (ref "U6") (pin "15") (pinfunction "PA5_15") (pintype "bidirectional"))
      (node (ref "U7") (pin "2") (pinfunction "2_2") (pintype "unspecified"))
    )
    (net (code "65") (name "SGND") (class "Default")
      (node (ref "C10") (pin "2") (pinfunction "2_2") (pintype "unspecified"))
      (node (ref "C11") (pin "2") (pinfunction "2_2") (pintype "unspecified"))
      (node (ref "C12") (pin "1") (pinfunction "1_1") (pintype "unspecified"))
      (node (ref "C13") (pin "1") (pinfunction "1_1") (pintype "unspecified"))
      (node (ref "C14") (pin "1") (pinfunction "1_1") (pintype "unspecified"))
      (node (ref "C15") (pin "1") (pinfunction "1_1") (pintype "unspecified"))
      (node (ref "C16") (pin "1") (pinfunction "1_1") (pintype "input"))
      (node (ref "C2") (pin "1") (pinfunction "1_1") (pintype "input"))
      (node (ref "C3") (pin "1") (pinfunction "1_1") (pintype "input"))
      (node (ref "C8") (pin "1") (pinfunction "1_1") (pintype "input"))
      (node (ref "C9") (pin "1") (pinfunction "1_1") (pintype "unspecified"))
      (node (ref "D3") (pin "2") (pinfunction "2_2") (pintype "unspecified"))
      (node (ref "D44") (pin "1") (pinfunction "1_1") (pintype "input"))
      (node (ref "P10") (pin "1") (pinfunction "1_1") (pintype "unspecified"))
      (node (ref "P9") (pin "1") (pinfunction "1_1") (pintype "input"))
      (node (ref "R14") (pin "1") (pinfunction "1_1") (pintype "unspecified"))
      (node (ref "R15") (pin "1") (pinfunction "1_1") (pintype "unspecified"))
      (node (ref "U1") (pin "4") (pinfunction "0V_4") (pintype "unspecified"))
      (node (ref "U3") (pin "1") (pinfunction "GND_1") (pintype "unspecified"))
      (node (ref "U4") (pin "3") (pinfunction "3_3") (pintype "unspecified"))
      (node (ref "U5") (pin "3") (pinfunction "3_3") (pintype "unspecified"))
      (node (ref "U6") (pin "23") (pinfunction "VSS_1_23") (pintype "unspecified"))
      (node (ref "U6") (pin "35") (pinfunction "VSS_2_35") (pintype "unspecified"))
      (node (ref "U6") (pin "47") (pinfunction "VSS_3_47") (pintype "unspecified"))
      (node (ref "U6") (pin "8") (pinfunction "VSSA_8") (pintype "unspecified"))
      (node (ref "U8") (pin "3") (pinfunction "3_3") (pintype "unspecified"))
    )
    (net (code "66") (name "SPINDLE_PWM") (class "Default")
      (node (ref "U6") (pin "29") (pinfunction "PA8_29") (pintype "bidirectional"))
    )
    (net (code "67") (name "SWCLK") (class "Default")
      (node (ref "P9") (pin "3") (pinfunction "3_3") (pintype "input"))
      (node (ref "U6") (pin "37") (pinfunction "PA14/JTCK/SWCLK_37") (pintype "bidirectional"))
    )
    (net (code "68") (name "SWDIO") (class "Default")
      (node (ref "P9") (pin "4") (pinfunction "4_4") (pintype "input"))
      (node (ref "U6") (pin "34") (pinfunction "PA13/JTMS/SWDIO_34") (pintype "bidirectional"))
    )
    (net (code "69") (name "TXD") (class "Default")
      (node (ref "P10") (pin "3") (pinfunction "3_3") (pintype "unspecified"))
      (node (ref "U6") (pin "30") (pinfunction "PA9_30") (pintype "bidirectional"))
    )
    (net (code "70") (name "VIN_24V") (class "Default")
      (node (ref "C6") (pin "1") (pinfunction "1_1") (pintype "input"))
      (node (ref "C7") (pin "2") (pinfunction "2_2") (pintype "unspecified"))
      (node (ref "D1") (pin "2") (pinfunction "2_2") (pintype "unspecified"))
      (node (ref "D10") (pin "2") (pinfunction "2_2") (pintype "unspecified"))
      (node (ref "D12") (pin "2") (pinfunction "2_2") (pintype "unspecified"))
      (node (ref "D5") (pin "2") (pinfunction "2_2") (pintype "unspecified"))
      (node (ref "K1") (pin "1") (pinfunction "1_1") (pintype "input"))
      (node (ref "K2") (pin "1") (pinfunction "1_1") (pintype "input"))
      (node (ref "K3") (pin "1") (pinfunction "1_1") (pintype "input"))
      (node (ref "R12") (pin "1") (pinfunction "1_1") (pintype "unspecified"))
      (node (ref "R16") (pin "2") (pinfunction "2_2") (pintype "unspecified"))
      (node (ref "R19") (pin "1") (pinfunction "1_1") (pintype "unspecified"))
      (node (ref "R2") (pin "1") (pinfunction "1_1") (pintype "unspecified"))
      (node (ref "R22") (pin "2") (pinfunction "2_2") (pintype "unspecified"))
      (node (ref "R24") (pin "1") (pinfunction "1_1") (pintype "unspecified"))
      (node (ref "R27") (pin "2") (pinfunction "2_2") (pintype "unspecified"))
      (node (ref "R29") (pin "1") (pinfunction "1_1") (pintype "unspecified"))
      (node (ref "R32") (pin "1") (pinfunction "1_1") (pintype "unspecified"))
      (node (ref "R4") (pin "2") (pinfunction "2_2") (pintype "unspecified"))
      (node (ref "R5") (pin "1") (pinfunction "1_1") (pintype "unspecified"))
      (node (ref "R9") (pin "1") (pinfunction "1_1") (pintype "unspecified"))
      (node (ref "U2") (pin "1") (pinfunction "VIN_1") (pintype "unspecified"))
    )
    (net (code "71") (name "XTAL1") (class "Default")
      (node (ref "C11") (pin "1") (pinfunction "1_1") (pintype "unspecified"))
      (node (ref "U6") (pin "5") (pinfunction "OSC_IN/PD0_5") (pintype "input"))
      (node (ref "Y1") (pin "1") (pinfunction "OSC1_1") (pintype "unspecified"))
    )
    (net (code "72") (name "XTAL2") (class "Default")
      (node (ref "C10") (pin "1") (pinfunction "1_1") (pintype "unspecified"))
      (node (ref "U6") (pin "6") (pinfunction "OSC_OUT/PD1_6") (pintype "output"))
      (node (ref "Y1") (pin "2") (pinfunction "OSC2_2") (pintype "unspecified"))
    )
    (net (code "73") (name "unconnected-(U6-PA15{slash}JTDI-Pad38)") (class "Default")
      (node (ref "U6") (pin "38") (pinfunction "PA15/JTDI_38") (pintype "bidirectional"))
    )
    (net (code "74") (name "unconnected-(U6-PB0-Pad18)") (class "Default")
      (node (ref "U6") (pin "18") (pinfunction "PB0_18") (pintype "bidirectional"))
    )
    (net (code "75") (name "unconnected-(U6-PB1-Pad19)") (class "Default")
      (node (ref "U6") (pin "19") (pinfunction "PB1_19") (pintype "bidirectional"))
    )
    (net (code "76") (name "unconnected-(U6-PB3{slash}JTDO-Pad39)") (class "Default")
      (node (ref "U6") (pin "39") (pinfunction "PB3/JTDO_39") (pintype "bidirectional"))
    )
    (net (code "77") (name "unconnected-(U6-PB4{slash}JNTRST-Pad40)") (class "Default")
      (node (ref "U6") (pin "40") (pinfunction "PB4/JNTRST_40") (pintype "bidirectional"))
    )
    (net (code "78") (name "unconnected-(U6-PB5-Pad41)") (class "Default")
      (node (ref "U6") (pin "41") (pinfunction "PB5_41") (pintype "bidirectional"))
    )
    (net (code "79") (name "unconnected-(U6-PB6-Pad42)") (class "Default")
      (node (ref "U6") (pin "42") (pinfunction "PB6_42") (pintype "bidirectional"))
    )
    (net (code "80") (name "unconnected-(U6-PB7-Pad43)") (class "Default")
      (node (ref "U6") (pin "43") (pinfunction "PB7_43") (pintype "bidirectional"))
    )
    (net (code "81") (name "unconnected-(U6-PB8-Pad45)") (class "Default")
      (node (ref "U6") (pin "45") (pinfunction "PB8_45") (pintype "bidirectional"))
    )
    (net (code "82") (name "unconnected-(U6-PB10-Pad21)") (class "Default")
      (node (ref "U6") (pin "21") (pinfunction "PB10_21") (pintype "bidirectional"))
    )
    (net (code "83") (name "unconnected-(U6-PB11-Pad22)") (class "Default")
      (node (ref "U6") (pin "22") (pinfunction "PB11_22") (pintype "bidirectional"))
    )
    (net (code "84") (name "unconnected-(U6-PC13-TAMPER-RTC-Pad2)") (class "Default")
      (node (ref "U6") (pin "2") (pinfunction "PC13-TAMPER-RTC_2") (pintype "bidirectional"))
    )
    (net (code "85") (name "unconnected-(U6-PC14-OSC32_IN-Pad3)") (class "Default")
      (node (ref "U6") (pin "3") (pinfunction "PC14-OSC32_IN_3") (pintype "bidirectional"))
    )
    (net (code "86") (name "unconnected-(U6-PC15-OSC32_OUT-Pad4)") (class "Default")
      (node (ref "U6") (pin "4") (pinfunction "PC15-OSC32_OUT_4") (pintype "bidirectional"))
    )
    (net (code "87") (name "unconnected-(U6-VBAT-Pad1)") (class "Default")
      (node (ref "U6") (pin "1") (pinfunction "VBAT_1") (pintype "unspecified"))
    )
  )
)
